# ST-LINK.net
KiCad netlist of a schematic drawn in Altium Designer
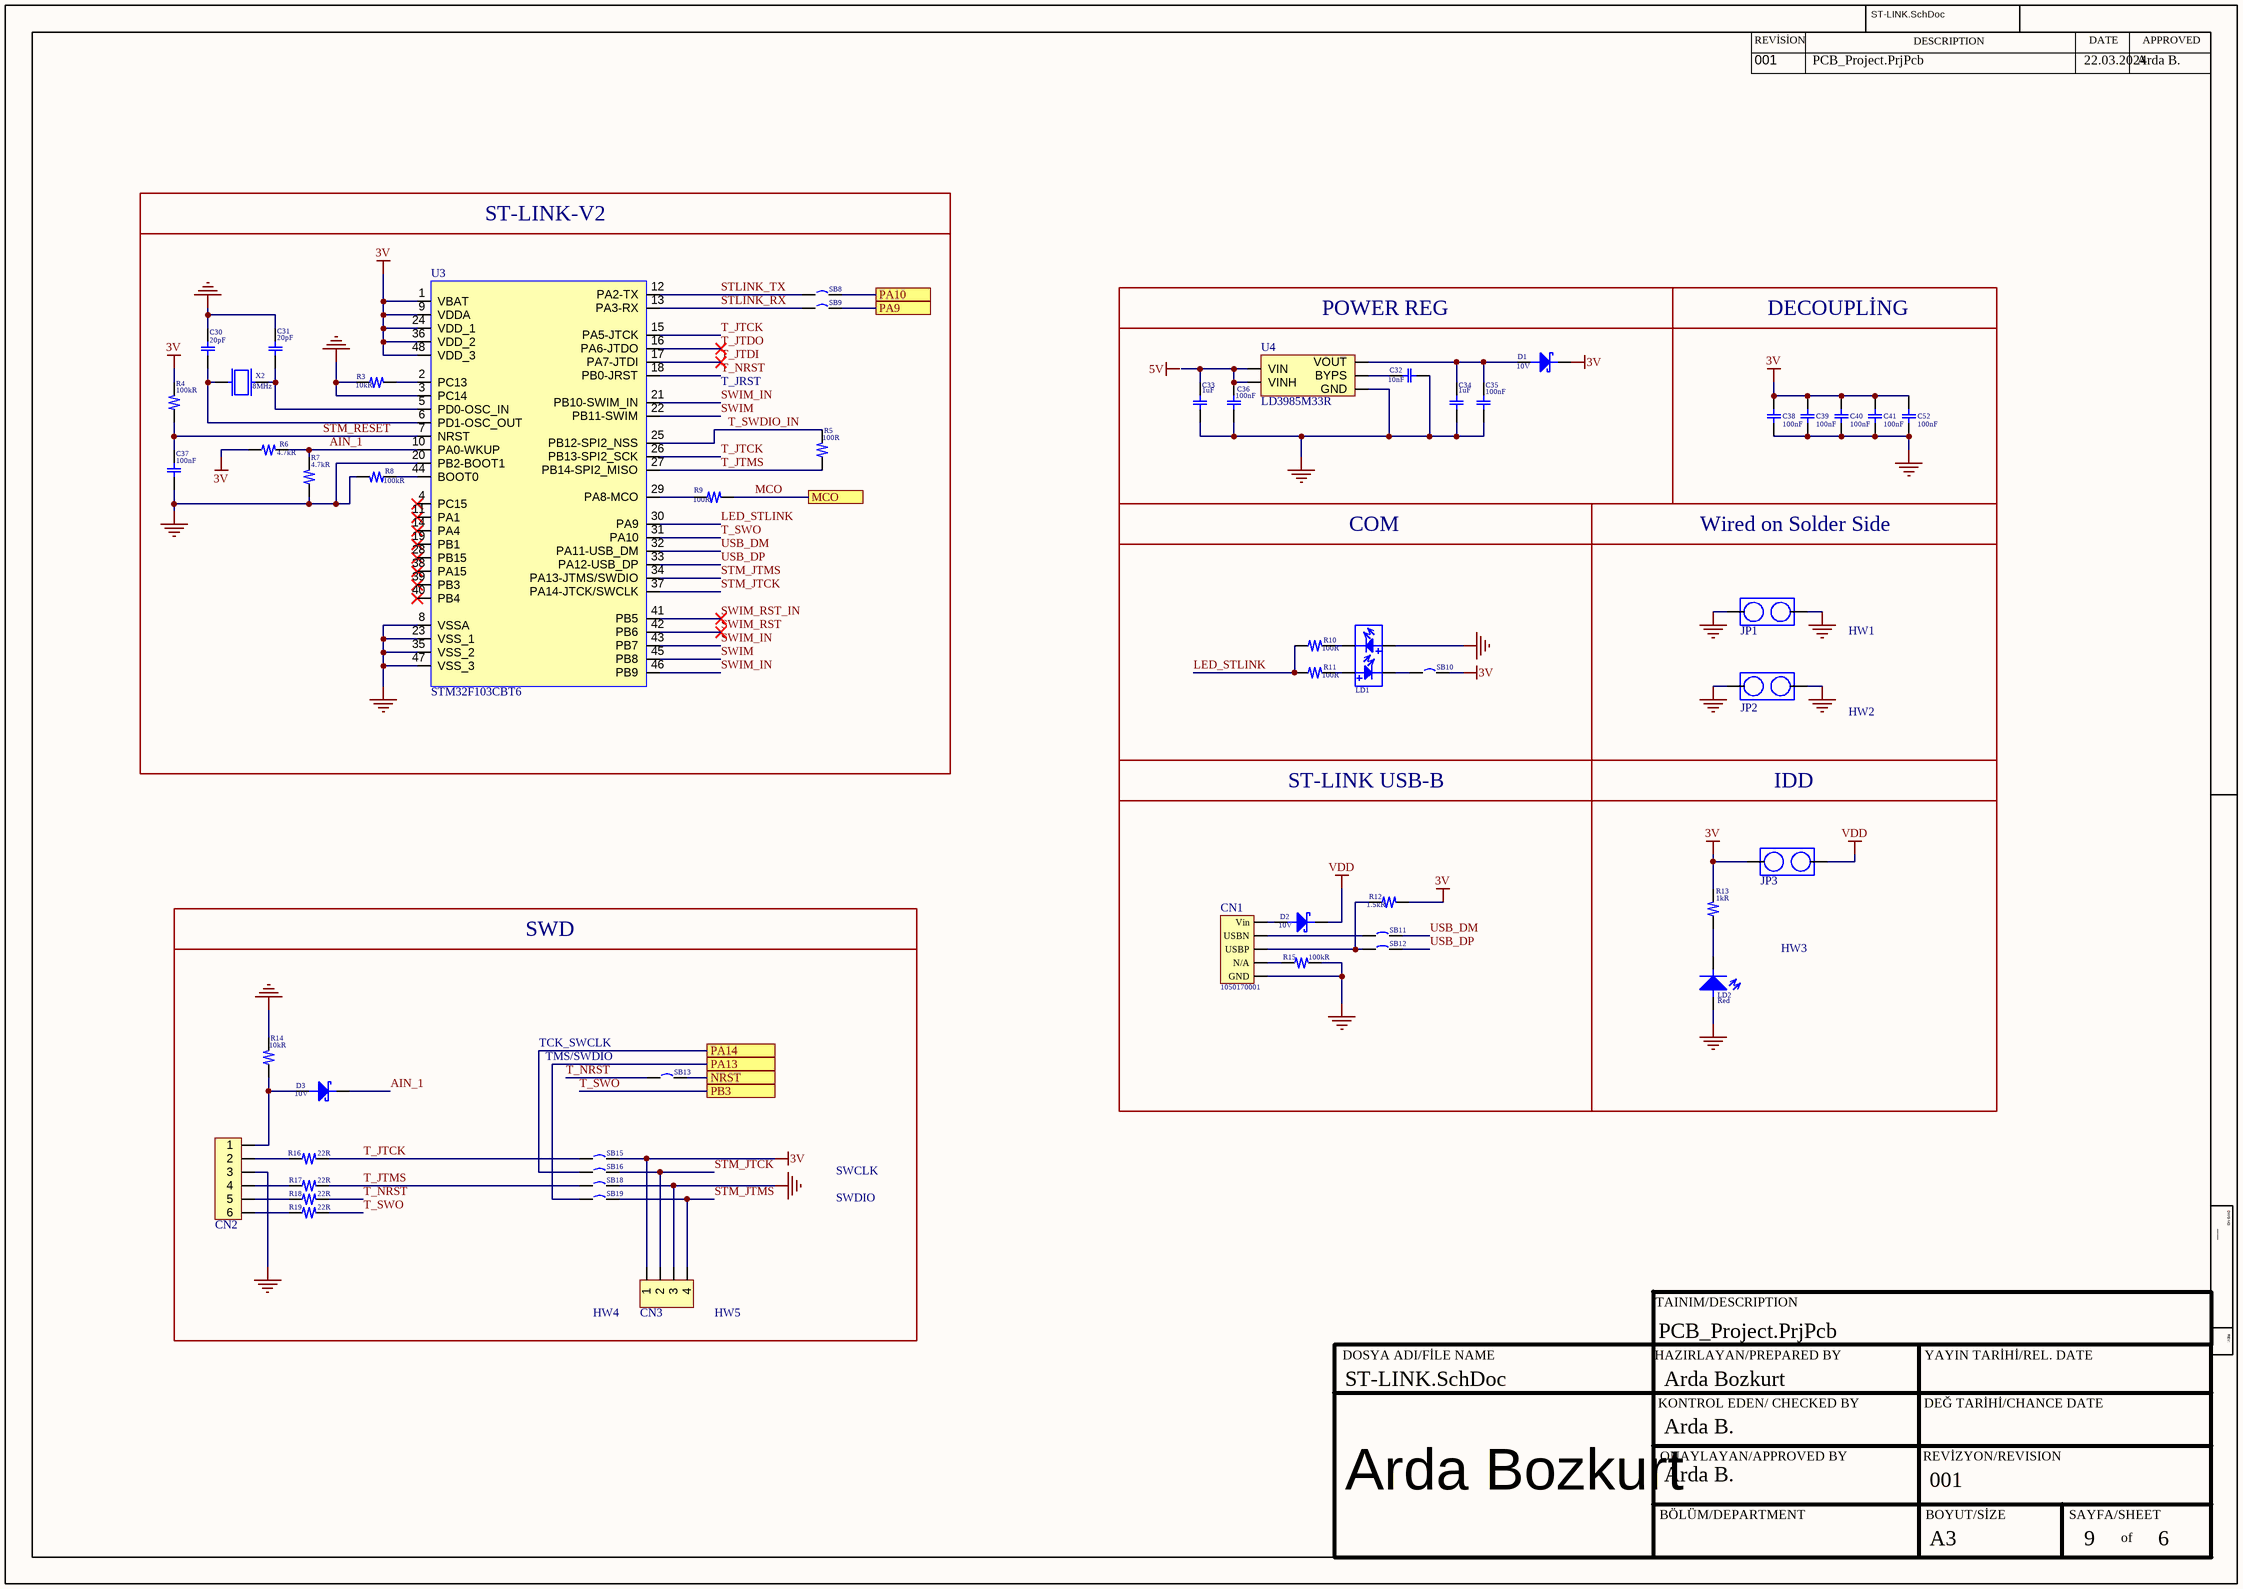
[diagram p0: ST-LINK.SchDoc]

(export (version "E")
  (design (tool "Eeschema 10.0.6"))
  (components
    (comp (ref "C30")
      (value "20pF")
      (footprint "CAP-0402")
      (description "CAP CER 20PF 50V C0G/NPO 0402")
      (fields
        (field (name "MANUFACTURER") "Yageo")
        (field (name "MANUFACTURER PART NUMBER") "CC0402JRNPO9BN200")
      )
      (libsource (lib "STM32") (part "CAP CER 20PF 50V C0G/NPO 0402"))
    )
    (comp (ref "C31")
      (value "20pF")
      (footprint "CAP-0402")
      (description "CAP CER 20PF 50V C0G/NPO 0402")
      (fields
        (field (name "MANUFACTURER") "Yageo")
        (field (name "MANUFACTURER PART NUMBER") "CC0402JRNPO9BN200")
      )
      (libsource (lib "STM32") (part "CAP CER 20PF 50V C0G/NPO 0402"))
    )
    (comp (ref "C32")
      (value "10nF")
      (footprint "CAP-0603")
      (description "Multilayer Ceramic Capacitor, 0.01 uF, 50 V, ± 10%, X7R, 0603 [1608 Metric]")
      (fields
        (field (name "MANUFACTURER") "Yageo")
        (field (name "MANUFACTURER PART NUMBER") "CC0603KRX7R9BB103")
      )
      (libsource (lib "STM32") (part "CAP CER 10nF 50V X7R 0603"))
    )
    (comp (ref "C33")
      (value "1uF")
      (footprint "CAP-0603")
      (description "Multilayer Ceramic Capacitor, 1 uF, 25 V, ± 10%, X5R, 0603 [1608 Metric]")
      (fields
        (field (name "MANUFACTURER") "Yageo")
        (field (name "MANUFACTURER PART NUMBER") "CC0603KRX5R8BB105")
      )
      (libsource (lib "STM32") (part "CAP CER 1UF 25V X5R 0603"))
    )
    (comp (ref "C34")
      (value "1uF")
      (footprint "CAP-0603")
      (description "Multilayer Ceramic Capacitor, 1 uF, 25 V, ± 10%, X5R, 0603 [1608 Metric]")
      (fields
        (field (name "MANUFACTURER") "Yageo")
        (field (name "MANUFACTURER PART NUMBER") "CC0603KRX5R8BB105")
      )
      (libsource (lib "STM32") (part "CAP CER 1UF 25V X5R 0603"))
    )
    (comp (ref "C35")
      (value "100nF")
      (footprint "CAP-0402")
      (description "Multilayer Ceramic Capacitor, 0.1 uF, 25 V, ± 10%, X7R, 0402 [1005 Metric]")
      (fields
        (field (name "MANUFACTURER") "Yageo")
        (field (name "MANUFACTURER PART NUMBER") "CC0402KRX7R7BB104")
      )
      (libsource (lib "STM32") (part "CAP CER 100nF 16V X7R 0402"))
    )
    (comp (ref "C36")
      (value "100nF")
      (footprint "CAP-0402")
      (description "Multilayer Ceramic Capacitor, 0.1 uF, 25 V, ± 10%, X7R, 0402 [1005 Metric]")
      (fields
        (field (name "MANUFACTURER") "Yageo")
        (field (name "MANUFACTURER PART NUMBER") "CC0402KRX7R7BB104")
      )
      (libsource (lib "STM32") (part "CAP CER 100nF 16V X7R 0402"))
    )
    (comp (ref "C37")
      (value "100nF")
      (footprint "CAP-0402")
      (description "Multilayer Ceramic Capacitor, 0.1 uF, 25 V, ± 10%, X7R, 0402 [1005 Metric]")
      (fields
        (field (name "MANUFACTURER") "Yageo")
        (field (name "MANUFACTURER PART NUMBER") "CC0402KRX7R7BB104")
      )
      (libsource (lib "STM32") (part "CAP CER 100nF 16V X7R 0402"))
    )
    (comp (ref "C38")
      (value "100nF")
      (footprint "CAP-0402")
      (description "Multilayer Ceramic Capacitor, 0.1 uF, 25 V, ± 10%, X7R, 0402 [1005 Metric]")
      (fields
        (field (name "MANUFACTURER") "Yageo")
        (field (name "MANUFACTURER PART NUMBER") "CC0402KRX7R7BB104")
      )
      (libsource (lib "STM32") (part "CAP CER 100nF 16V X7R 0402"))
    )
    (comp (ref "C39")
      (value "100nF")
      (footprint "CAP-0402")
      (description "Multilayer Ceramic Capacitor, 0.1 uF, 25 V, ± 10%, X7R, 0402 [1005 Metric]")
      (fields
        (field (name "MANUFACTURER") "Yageo")
        (field (name "MANUFACTURER PART NUMBER") "CC0402KRX7R7BB104")
      )
      (libsource (lib "STM32") (part "CAP CER 100nF 16V X7R 0402"))
    )
    (comp (ref "C40")
      (value "100nF")
      (footprint "CAP-0402")
      (description "Multilayer Ceramic Capacitor, 0.1 uF, 25 V, ± 10%, X7R, 0402 [1005 Metric]")
      (fields
        (field (name "MANUFACTURER") "Yageo")
        (field (name "MANUFACTURER PART NUMBER") "CC0402KRX7R7BB104")
      )
      (libsource (lib "STM32") (part "CAP CER 100nF 16V X7R 0402"))
    )
    (comp (ref "C41")
      (value "100nF")
      (footprint "CAP-0402")
      (description "Multilayer Ceramic Capacitor, 0.1 uF, 25 V, ± 10%, X7R, 0402 [1005 Metric]")
      (fields
        (field (name "MANUFACTURER") "Yageo")
        (field (name "MANUFACTURER PART NUMBER") "CC0402KRX7R7BB104")
      )
      (libsource (lib "STM32") (part "CAP CER 100nF 16V X7R 0402"))
    )
    (comp (ref "C52")
      (value "100nF")
      (footprint "CAP-0402")
      (description "Multilayer Ceramic Capacitor, 0.1 uF, 25 V, ± 10%, X7R, 0402 [1005 Metric]")
      (fields
        (field (name "MANUFACTURER") "Yageo")
        (field (name "MANUFACTURER PART NUMBER") "CC0402KRX7R7BB104")
      )
      (libsource (lib "STM32") (part "CAP CER 100nF 16V X7R 0402"))
    )
    (comp (ref "CN1")
      (value "1050170001")
      (footprint "USB MİCRO B")
      (description "Conn Micro USB 2.0 Type B RCP 5 POS 0.65mm Solder RA SMD 5 Terminal 1 Port Micro-USB T/R")
      (fields (field (name "MANUFACTURER") "Molex"))
      (libsource (lib "STM32") (part "CONN USB MICRO B SMD"))
    )
    (comp (ref "CN2")
      (value "TS-106-G-A")
      (footprint "CONN-6POS")
      (description "Conn Unshrouded Header HDR 6 POS 2.54mm Solder ST Top Entry Thru-Hole Tube")
      (fields (field (name "MANUFACTURER") "Samtec"))
      (libsource (lib "STM32") (part "CONN 6POS"))
    )
    (comp (ref "CN3")
      (value "61300411121")
      (footprint "CONN-4POS")
      (description "THT Vertical Pin Header WR-PHD, Pitch 2.54 mm, Single Row, 4 pins")
      (fields (field (name "MANUFACTURER") "Wurth Electronics"))
      (libsource (lib "STM32") (part "CONN 4POS GOLD"))
    )
    (comp (ref "D1")
      (value "BAT60JFILM")
      (footprint "SOD-323")
      (description "Rectifier Diode, Schottky, 1 Phase, 1 Element, 3A, 10V V(RRM), Silicon")
      (fields (field (name "MANUFACTURER") "STMicroelectronics") (field (name "PEAK VOLTAGE") "10V"))
      (libsource (lib "STM32") (part "DIODE SCHOTTKY 10V 3A SOD323"))
    )
    (comp (ref "D2")
      (value "BAT60JFILM")
      (footprint "SOD-323")
      (description "Rectifier Diode, Schottky, 1 Phase, 1 Element, 3A, 10V V(RRM), Silicon")
      (fields (field (name "MANUFACTURER") "STMicroelectronics") (field (name "PEAK VOLTAGE") "10V"))
      (libsource (lib "STM32") (part "DIODE SCHOTTKY 10V 3A SOD323"))
    )
    (comp (ref "D3")
      (value "BAT60JFILM")
      (footprint "SOD-323")
      (description "Rectifier Diode, Schottky, 1 Phase, 1 Element, 3A, 10V V(RRM), Silicon")
      (fields (field (name "MANUFACTURER") "STMicroelectronics") (field (name "PEAK VOLTAGE") "10V"))
      (libsource (lib "STM32") (part "DIODE SCHOTTKY 10V 3A SOD323"))
    )
    (comp (ref "HW1")
      (value "MNT-101-BK-G")
      (footprint "SHUNT")
      (description "MNT - Samtec 2.54mm Multi Position Jumper Link / Shunt")
      (fields (field (name "MANUFACTURER") "Samtec"))
      (libsource (lib "STM32") (part "SHUNT"))
    )
    (comp (ref "HW2")
      (value "MNT-101-BK-G")
      (footprint "SHUNT")
      (description "MNT - Samtec 2.54mm Multi Position Jumper Link / Shunt")
      (fields (field (name "MANUFACTURER") "Samtec"))
      (libsource (lib "STM32") (part "SHUNT"))
    )
    (comp (ref "HW3")
      (value "MNT-101-BK-G")
      (footprint "SHUNT")
      (description "MNT - Samtec 2.54mm Multi Position Jumper Link / Shunt")
      (fields (field (name "MANUFACTURER") "Samtec"))
      (libsource (lib "STM32") (part "SHUNT"))
    )
    (comp (ref "HW4")
      (value "MNT-101-BK-G")
      (footprint "SHUNT")
      (description "MNT - Samtec 2.54mm Multi Position Jumper Link / Shunt")
      (fields (field (name "MANUFACTURER") "Samtec"))
      (libsource (lib "STM32") (part "SHUNT"))
    )
    (comp (ref "HW5")
      (value "MNT-101-BK-G")
      (footprint "SHUNT")
      (description "MNT - Samtec 2.54mm Multi Position Jumper Link / Shunt")
      (fields (field (name "MANUFACTURER") "Samtec"))
      (libsource (lib "STM32") (part "SHUNT"))
    )
    (comp (ref "JP1")
      (value "61300211121")
      (footprint "CONN-2PİNS")
      (description "THT Vertical Pin Header WR-PHD, Pitch 2.54 mm, Single Row, 2 pins")
      (fields (field (name "MANUFACTURER") "Wurth Electronics"))
      (libsource (lib "STM32") (part "CONN HEADER VERT 2POS 2.54MM"))
    )
    (comp (ref "JP2")
      (value "61300211121")
      (footprint "CONN-2PİNS")
      (description "THT Vertical Pin Header WR-PHD, Pitch 2.54 mm, Single Row, 2 pins")
      (fields (field (name "MANUFACTURER") "Wurth Electronics"))
      (libsource (lib "STM32") (part "CONN HEADER VERT 2POS 2.54MM"))
    )
    (comp (ref "JP3")
      (value "61300211121")
      (footprint "CONN-2PİNS")
      (description "THT Vertical Pin Header WR-PHD, Pitch 2.54 mm, Single Row, 2 pins")
      (fields (field (name "MANUFACTURER") "Wurth Electronics"))
      (libsource (lib "STM32") (part "CONN HEADER VERT 2POS 2.54MM"))
    )
    (comp (ref "LD1")
      (value "67-22SURSYGC/S530-A2/TR8")
      (footprint "LED-RED-GREEN-SMD")
      (description "LED Bi-Color Red/Yellow Green 632nm/575nm 4-Pin PLCC T/R")
      (fields (field (name "MANUFACTURER") "Everlight"))
      (libsource (lib "STM32") (part "LED Red/Yellow-Green SMD"))
    )
    (comp (ref "LD2")
      (value "150060RS75000")
      (footprint "LED-RED-0603")
      (description "LED Low-Power Uni-Color Red 630nm 2V 2-Pin Chip 0603(1608Metric) T/R")
      (fields (field (name "MANUFACTURER") "Wurth Electronics") (field (name "COLOR") "Red"))
      (libsource (lib "STM32") (part "LED RED CLEAR 0603 SMD"))
    )
    (comp (ref "R3")
      (value "10kR")
      (footprint "RES-0402")
      (description "SMD Chip Resistor, 10 kOhm, ± 1%, 63 mW, 0402 [1005 Metric], Thick Film, General Purpose")
      (fields
        (field (name "MANUFACTURER") "Yageo")
        (field (name "MANUFACTURER PART NUMBER") "RC0402FR-0710KL")
      )
      (libsource (lib "STM32") (part "RES 10K OHM 1% 1/16W 0402"))
    )
    (comp (ref "R4")
      (value "100kR")
      (footprint "RES-0402")
      (description "SMD Chip Resistor, 100 kOhm, ± 1%, 63 mW, 0402 [1005 Metric], Thick Film, General Purpose")
      (fields
        (field (name "MANUFACTURER") "Yageo")
        (field (name "MANUFACTURER PART NUMBER") "RC0402FR-07100KL")
      )
      (libsource (lib "STM32") (part "RES 100K OHM 1% 1/16W 0402"))
    )
    (comp (ref "R5")
      (value "100R")
      (footprint "RES-0402")
      (description "SMD Chip Resistor, 100 Ohm, ± 1%, 63 mW, 0402 [1005 Metric], Thick Film, General Purpose")
      (fields
        (field (name "MANUFACTURER") "Yageo")
        (field (name "MANUFACTURER PART NUMBER") "RC0402FR-07100RL")
      )
      (libsource (lib "STM32") (part "RES 100 OHM 1% 1/16W 0402"))
    )
    (comp (ref "R6")
      (value "4.7kR")
      (footprint "RES-0402")
      (description "SMD Chip Resistor, 4.7 kOhm, ± 1%, 63 mW, 0402 [1005 Metric], Thick Film, General Purpose")
      (fields
        (field (name "MANUFACTURER") "Yageo")
        (field (name "MANUFACTURER PART NUMBER") "RC0402FR-074K7L")
      )
      (libsource (lib "STM32") (part "RES 4.7K OHM 1% 1/16W 0402"))
    )
    (comp (ref "R7")
      (value "4.7kR")
      (footprint "RES-0402")
      (description "SMD Chip Resistor, 4.7 kOhm, ± 1%, 63 mW, 0402 [1005 Metric], Thick Film, General Purpose")
      (fields
        (field (name "MANUFACTURER") "Yageo")
        (field (name "MANUFACTURER PART NUMBER") "RC0402FR-074K7L")
      )
      (libsource (lib "STM32") (part "RES 4.7K OHM 1% 1/16W 0402"))
    )
    (comp (ref "R8")
      (value "100kR")
      (footprint "RES-0402")
      (description "SMD Chip Resistor, 100 kOhm, ± 1%, 63 mW, 0402 [1005 Metric], Thick Film, General Purpose")
      (fields
        (field (name "MANUFACTURER") "Yageo")
        (field (name "MANUFACTURER PART NUMBER") "RC0402FR-07100KL")
      )
      (libsource (lib "STM32") (part "RES 100K OHM 1% 1/16W 0402"))
    )
    (comp (ref "R9")
      (value "100R")
      (footprint "RES-0402")
      (description "SMD Chip Resistor, 100 Ohm, ± 1%, 63 mW, 0402 [1005 Metric], Thick Film, General Purpose")
      (fields
        (field (name "MANUFACTURER") "Yageo")
        (field (name "MANUFACTURER PART NUMBER") "RC0402FR-07100RL")
      )
      (libsource (lib "STM32") (part "RES 100 OHM 1% 1/16W 0402"))
    )
    (comp (ref "R10")
      (value "100R")
      (footprint "RES-0402")
      (description "SMD Chip Resistor, 100 Ohm, ± 1%, 63 mW, 0402 [1005 Metric], Thick Film, General Purpose")
      (fields
        (field (name "MANUFACTURER") "Yageo")
        (field (name "MANUFACTURER PART NUMBER") "RC0402FR-07100RL")
      )
      (libsource (lib "STM32") (part "RES 100 OHM 1% 1/16W 0402"))
    )
    (comp (ref "R11")
      (value "100R")
      (footprint "RES-0402")
      (description "SMD Chip Resistor, 100 Ohm, ± 1%, 63 mW, 0402 [1005 Metric], Thick Film, General Purpose")
      (fields
        (field (name "MANUFACTURER") "Yageo")
        (field (name "MANUFACTURER PART NUMBER") "RC0402FR-07100RL")
      )
      (libsource (lib "STM32") (part "RES 100 OHM 1% 1/16W 0402"))
    )
    (comp (ref "R12")
      (value "1.5kR")
      (footprint "RES-0402")
      (description "SMD Chip Resistor, 1.5 kOhm, ± 1%, 63 mW, 0402 [1005 Metric], Thick Film, General Purpose")
      (fields
        (field (name "MANUFACTURER") "Yageo")
        (field (name "MANUFACTURER PART NUMBER") "RC0402FR-071K5L")
      )
      (libsource (lib "STM32") (part "RES 1.5K OHM 1% 1/16W 0402"))
    )
    (comp (ref "R13")
      (value "1kR")
      (footprint "RES-0402")
      (description "SMD Chip Resistor, 1 kOhm, ± 1%, 63 mW, 0402 [1005 Metric], Thick Film, General Purpose")
      (fields
        (field (name "MANUFACTURER") "Yageo")
        (field (name "MANUFACTURER PART NUMBER") "RC0402FR-071KL")
      )
      (libsource (lib "STM32") (part "RES 1K OHM 1% 1/16W 0402"))
    )
    (comp (ref "R14")
      (value "10kR")
      (footprint "RES-0402")
      (description "SMD Chip Resistor, 10 kOhm, ± 1%, 63 mW, 0402 [1005 Metric], Thick Film, General Purpose")
      (fields
        (field (name "MANUFACTURER") "Yageo")
        (field (name "MANUFACTURER PART NUMBER") "RC0402FR-0710KL")
      )
      (libsource (lib "STM32") (part "RES 10K OHM 1% 1/16W 0402"))
    )
    (comp (ref "R15")
      (value "100kR")
      (footprint "RES-0402")
      (description "SMD Chip Resistor, 100 kOhm, ± 1%, 63 mW, 0402 [1005 Metric], Thick Film, General Purpose")
      (fields
        (field (name "MANUFACTURER") "Yageo")
        (field (name "MANUFACTURER PART NUMBER") "RC0402FR-07100KL")
      )
      (libsource (lib "STM32") (part "RES 100K OHM 1% 1/16W 0402"))
    )
    (comp (ref "R16")
      (value "22R")
      (footprint "RES-0603")
      (description "SMD Chip Resistor, 22 Ohm, ± 1%, 100 mW, 0603 [1608 Metric], Thick Film, General Purpose")
      (fields
        (field (name "MANUFACTURER") "Yageo")
        (field (name "MANUFACTURER PART NUMBER") "RC0603FR-0722RL")
      )
      (libsource (lib "STM32") (part "RES 22 OHM 1% 1/10W 0603"))
    )
    (comp (ref "R17")
      (value "22R")
      (footprint "RES-0603")
      (description "SMD Chip Resistor, 22 Ohm, ± 1%, 100 mW, 0603 [1608 Metric], Thick Film, General Purpose")
      (fields
        (field (name "MANUFACTURER") "Yageo")
        (field (name "MANUFACTURER PART NUMBER") "RC0603FR-0722RL")
      )
      (libsource (lib "STM32") (part "RES 22 OHM 1% 1/10W 0603"))
    )
    (comp (ref "R18")
      (value "22R")
      (footprint "RES-0603")
      (description "SMD Chip Resistor, 22 Ohm, ± 1%, 100 mW, 0603 [1608 Metric], Thick Film, General Purpose")
      (fields
        (field (name "MANUFACTURER") "Yageo")
        (field (name "MANUFACTURER PART NUMBER") "RC0603FR-0722RL")
      )
      (libsource (lib "STM32") (part "RES 22 OHM 1% 1/10W 0603"))
    )
    (comp (ref "R19")
      (value "22R")
      (footprint "RES-0603")
      (description "SMD Chip Resistor, 22 Ohm, ± 1%, 100 mW, 0603 [1608 Metric], Thick Film, General Purpose")
      (fields
        (field (name "MANUFACTURER") "Yageo")
        (field (name "MANUFACTURER PART NUMBER") "RC0603FR-0722RL")
      )
      (libsource (lib "STM32") (part "RES 22 OHM 1% 1/10W 0603"))
    )
    (comp (ref "SB8")
      (value "RC0402JR-070RL")
      (footprint "RES-0402")
      (description "Zero Ohm Resistor, Jumper, 0402 [1005 Metric], Thick Film, 62.5 mW, 1 A, Surface Mount")
      (fields
        (field (name "MANUFACTURER") "Yageo")
        (field (name "MANUFACTURER PART NUMBER") "RC0603JR-070RL")
      )
      (libsource (lib "STM32") (part "RES 0 OHM JUMPER 1/10W 0603"))
    )
    (comp (ref "SB9")
      (value "RC0402JR-070RL")
      (footprint "RES-0402")
      (description "Zero Ohm Resistor, Jumper, 0402 [1005 Metric], Thick Film, 62.5 mW, 1 A, Surface Mount")
      (fields
        (field (name "MANUFACTURER") "Yageo")
        (field (name "MANUFACTURER PART NUMBER") "RC0603JR-070RL")
      )
      (libsource (lib "STM32") (part "RES 0 OHM JUMPER 1/10W 0603"))
    )
    (comp (ref "SB10")
      (value "RC0402JR-070RL")
      (footprint "RES-0402")
      (description "Zero Ohm Resistor, Jumper, 0402 [1005 Metric], Thick Film, 62.5 mW, 1 A, Surface Mount")
      (fields
        (field (name "MANUFACTURER") "Yageo")
        (field (name "MANUFACTURER PART NUMBER") "RC0603JR-070RL")
      )
      (libsource (lib "STM32") (part "RES 0 OHM JUMPER 1/10W 0603"))
    )
    (comp (ref "SB11")
      (value "RC0402JR-070RL")
      (footprint "RES-0402")
      (description "Zero Ohm Resistor, Jumper, 0402 [1005 Metric], Thick Film, 62.5 mW, 1 A, Surface Mount")
      (fields
        (field (name "MANUFACTURER") "Yageo")
        (field (name "MANUFACTURER PART NUMBER") "RC0603JR-070RL")
      )
      (libsource (lib "STM32") (part "RES 0 OHM JUMPER 1/10W 0603"))
    )
    (comp (ref "SB12")
      (value "RC0402JR-070RL")
      (footprint "RES-0402")
      (description "Zero Ohm Resistor, Jumper, 0402 [1005 Metric], Thick Film, 62.5 mW, 1 A, Surface Mount")
      (fields
        (field (name "MANUFACTURER") "Yageo")
        (field (name "MANUFACTURER PART NUMBER") "RC0603JR-070RL")
      )
      (libsource (lib "STM32") (part "RES 0 OHM JUMPER 1/10W 0603"))
    )
    (comp (ref "SB13")
      (value "RC0402JR-070RL")
      (footprint "RES-0402")
      (description "Zero Ohm Resistor, Jumper, 0402 [1005 Metric], Thick Film, 62.5 mW, 1 A, Surface Mount")
      (fields
        (field (name "MANUFACTURER") "Yageo")
        (field (name "MANUFACTURER PART NUMBER") "RC0603JR-070RL")
      )
      (libsource (lib "STM32") (part "RES 0 OHM JUMPER 1/10W 0603"))
    )
    (comp (ref "SB15")
      (value "RC0402JR-070RL")
      (footprint "RES-0402")
      (description "Zero Ohm Resistor, Jumper, 0402 [1005 Metric], Thick Film, 62.5 mW, 1 A, Surface Mount")
      (fields
        (field (name "MANUFACTURER") "Yageo")
        (field (name "MANUFACTURER PART NUMBER") "RC0603JR-070RL")
      )
      (libsource (lib "STM32") (part "RES 0 OHM JUMPER 1/10W 0603"))
    )
    (comp (ref "SB16")
      (value "RC0402JR-070RL")
      (footprint "RES-0402")
      (description "Zero Ohm Resistor, Jumper, 0402 [1005 Metric], Thick Film, 62.5 mW, 1 A, Surface Mount")
      (fields
        (field (name "MANUFACTURER") "Yageo")
        (field (name "MANUFACTURER PART NUMBER") "RC0603JR-070RL")
      )
      (libsource (lib "STM32") (part "RES 0 OHM JUMPER 1/10W 0603"))
    )
    (comp (ref "SB18")
      (value "RC0402JR-070RL")
      (footprint "RES-0402")
      (description "Zero Ohm Resistor, Jumper, 0402 [1005 Metric], Thick Film, 62.5 mW, 1 A, Surface Mount")
      (fields
        (field (name "MANUFACTURER") "Yageo")
        (field (name "MANUFACTURER PART NUMBER") "RC0603JR-070RL")
      )
      (libsource (lib "STM32") (part "RES 0 OHM JUMPER 1/10W 0603"))
    )
    (comp (ref "SB19")
      (value "RC0402JR-070RL")
      (footprint "RES-0402")
      (description "Zero Ohm Resistor, Jumper, 0402 [1005 Metric], Thick Film, 62.5 mW, 1 A, Surface Mount")
      (fields
        (field (name "MANUFACTURER") "Yageo")
        (field (name "MANUFACTURER PART NUMBER") "RC0603JR-070RL")
      )
      (libsource (lib "STM32") (part "RES 0 OHM JUMPER 1/10W 0603"))
    )
    (comp (ref "U3")
      (value "STM32F103CBT6")
      (footprint "LQFP-48")
      (description "ARM Cortex-M3 STM32 F1 Microcontroller 32-Bit 72MHz 128kB FLASH LQFP48 STM32F103CBT6")
      (fields (field (name "MANUFACTURER") "STMicroelectronics"))
      (libsource (lib "STM32") (part "IC MCU 32BIT 128KB FLASH 48LQFP"))
    )
    (comp (ref "U4")
      (value "LD3985M33R")
      (footprint "SOT23-5L")
      (description "LD3985 Series 150 mA 3.3 V Fixed Low Noise LDO BiCMOS Regulator-SOT-23-5")
      (fields (field (name "MANUFACTURER") "STMicroelectronics"))
      (libsource (lib "STM32") (part "IC REG LINEAR 3.3V 150MA SOT23-5"))
    )
    (comp (ref "X2")
      (value "H1OED8K5SC-112YXC-8M")
      (footprint "HC-49US")
      (description "HC-49US 8MHZ 20PF 20PPM H1OED8K5")
      (fields (field (name "MANUFACTURER") "YXC") (field (name "FREQUENCY") "8MHz"))
      (libsource (lib "STM32") (part "Crystal 8MHZ 20PF 20PPM H1OED8K5"))
    )
  )
  (nets
    (net (code "1") (name "/AIN_1") (class "Default")
      (node (ref "D3") (pin "1") (pinfunction "1_1") (pintype "passive"))
      (node (ref "R6") (pin "2") (pinfunction "2_2") (pintype "passive"))
      (node (ref "R7") (pin "2") (pinfunction "2_2") (pintype "passive"))
      (node (ref "U3") (pin "10") (pinfunction "PA0-WKUP_10") (pintype "passive"))
    )
    (net (code "2") (name "/LED_STLINK") (class "Default")
      (node (ref "R10") (pin "1") (pinfunction "1_1") (pintype "passive"))
      (node (ref "R11") (pin "1") (pinfunction "1_1") (pintype "passive"))
      (node (ref "U3") (pin "30") (pinfunction "PA9_30") (pintype "passive"))
    )
    (net (code "3") (name "/MCO") (class "Default")
      (node (ref "R9") (pin "2") (pinfunction "2_2") (pintype "passive"))
    )
    (net (code "4") (name "/NRST") (class "Default")
      (node (ref "SB13") (pin "2") (pinfunction "2_2") (pintype "passive"))
    )
    (net (code "5") (name "/PA9") (class "Default")
      (node (ref "SB9") (pin "2") (pinfunction "2_2") (pintype "passive"))
    )
    (net (code "6") (name "/PA10") (class "Default")
      (node (ref "SB8") (pin "2") (pinfunction "2_2") (pintype "passive"))
    )
    (net (code "7") (name "/PA13") (class "Default")
      (node (ref "SB19") (pin "1") (pinfunction "1_1") (pintype "passive"))
    )
    (net (code "8") (name "/PA14") (class "Default")
      (node (ref "SB16") (pin "1") (pinfunction "1_1") (pintype "passive"))
    )
    (net (code "9") (name "/STLINK_RX") (class "Default")
      (node (ref "SB9") (pin "1") (pinfunction "1_1") (pintype "passive"))
      (node (ref "U3") (pin "13") (pinfunction "PA3-RX_13") (pintype "passive"))
    )
    (net (code "10") (name "/STLINK_TX") (class "Default")
      (node (ref "SB8") (pin "1") (pinfunction "1_1") (pintype "passive"))
      (node (ref "U3") (pin "12") (pinfunction "PA2-TX_12") (pintype "passive"))
    )
    (net (code "11") (name "/STM_JTCK") (class "Default")
      (node (ref "CN3") (pin "2") (pinfunction "2_2") (pintype "passive"))
      (node (ref "SB16") (pin "2") (pinfunction "2_2") (pintype "passive"))
      (node (ref "U3") (pin "37") (pinfunction "PA14-JTCK/SWCLK_37") (pintype "passive"))
    )
    (net (code "12") (name "/STM_JTMS") (class "Default")
      (node (ref "CN3") (pin "4") (pinfunction "4_4") (pintype "passive"))
      (node (ref "SB19") (pin "2") (pinfunction "2_2") (pintype "passive"))
      (node (ref "U3") (pin "34") (pinfunction "PA13-JTMS/SWDIO_34") (pintype "passive"))
    )
    (net (code "13") (name "/STM_RESET") (class "Default")
      (node (ref "C37") (pin "2") (pinfunction "2_2") (pintype "passive"))
      (node (ref "R4") (pin "1") (pinfunction "1_1") (pintype "passive"))
      (node (ref "U3") (pin "7") (pinfunction "NRST_7") (pintype "passive"))
    )
    (net (code "14") (name "/SWIM") (class "Default")
      (node (ref "U3") (pin "22") (pinfunction "PB11-SWIM_22") (pintype "passive"))
      (node (ref "U3") (pin "45") (pinfunction "PB8_45") (pintype "passive"))
    )
    (net (code "15") (name "/SWIM_IN") (class "Default")
      (node (ref "U3") (pin "21") (pinfunction "PB10-SWIM_IN_21") (pintype "passive"))
      (node (ref "U3") (pin "43") (pinfunction "PB7_43") (pintype "passive"))
      (node (ref "U3") (pin "46") (pinfunction "PB9_46") (pintype "passive"))
    )
    (net (code "16") (name "/SWIM_RST") (class "Default")
      (node (ref "U3") (pin "42") (pinfunction "PB6_42") (pintype "passive+no_connect"))
    )
    (net (code "17") (name "/SWIM_RST_IN") (class "Default")
      (node (ref "U3") (pin "41") (pinfunction "PB5_41") (pintype "passive+no_connect"))
    )
    (net (code "18") (name "/T_JTCK") (class "Default")
      (node (ref "R16") (pin "2") (pinfunction "2_2") (pintype "passive"))
      (node (ref "SB15") (pin "1") (pinfunction "1_1") (pintype "passive"))
      (node (ref "U3") (pin "15") (pinfunction "PA5-JTCK_15") (pintype "passive"))
      (node (ref "U3") (pin "26") (pinfunction "PB13-SPI2_SCK_26") (pintype "passive"))
    )
    (net (code "19") (name "/T_JTDI") (class "Default")
      (node (ref "U3") (pin "17") (pinfunction "PA7-JTDI_17") (pintype "passive+no_connect"))
    )
    (net (code "20") (name "/T_JTDO") (class "Default")
      (node (ref "U3") (pin "16") (pinfunction "PA6-JTDO_16") (pintype "passive+no_connect"))
    )
    (net (code "21") (name "/T_JTMS") (class "Default")
      (node (ref "R17") (pin "2") (pinfunction "2_2") (pintype "passive"))
      (node (ref "R5") (pin "1") (pinfunction "1_1") (pintype "passive"))
      (node (ref "SB18") (pin "1") (pinfunction "1_1") (pintype "passive"))
      (node (ref "U3") (pin "27") (pinfunction "PB14-SPI2_MISO_27") (pintype "passive"))
    )
    (net (code "22") (name "/T_NRST") (class "Default")
      (node (ref "R18") (pin "2") (pinfunction "2_2") (pintype "passive"))
      (node (ref "SB13") (pin "1") (pinfunction "1_1") (pintype "passive"))
      (node (ref "U3") (pin "18") (pinfunction "PB0-JRST_18") (pintype "passive"))
    )
    (net (code "23") (name "/T_SWDIO_IN") (class "Default")
      (node (ref "R5") (pin "2") (pinfunction "2_2") (pintype "passive"))
      (node (ref "U3") (pin "25") (pinfunction "PB12-SPI2_NSS_25") (pintype "passive"))
    )
    (net (code "24") (name "/T_SWO") (class "Default")
      (node (ref "R19") (pin "2") (pinfunction "2_2") (pintype "passive"))
      (node (ref "U3") (pin "31") (pinfunction "PA10_31") (pintype "passive"))
    )
    (net (code "25") (name "/USB_DM") (class "Default")
      (node (ref "SB11") (pin "2") (pinfunction "2_2") (pintype "passive"))
      (node (ref "U3") (pin "32") (pinfunction "PA11-USB_DM_32") (pintype "passive"))
    )
    (net (code "26") (name "/USB_DP") (class "Default")
      (node (ref "SB12") (pin "2") (pinfunction "2_2") (pintype "passive"))
      (node (ref "U3") (pin "33") (pinfunction "PA12-USB_DP_33") (pintype "passive"))
    )
    (net (code "27") (name "3V") (class "Default")
      (node (ref "C38") (pin "2") (pinfunction "2_2") (pintype "passive"))
      (node (ref "C39") (pin "2") (pinfunction "2_2") (pintype "passive"))
      (node (ref "C40") (pin "2") (pinfunction "2_2") (pintype "passive"))
      (node (ref "C41") (pin "2") (pinfunction "2_2") (pintype "passive"))
      (node (ref "C52") (pin "2") (pinfunction "2_2") (pintype "passive"))
      (node (ref "CN3") (pin "1") (pinfunction "1_1") (pintype "passive"))
      (node (ref "D1") (pin "1") (pinfunction "1_1") (pintype "passive"))
      (node (ref "JP3") (pin "1") (pinfunction "1_1") (pintype "passive"))
      (node (ref "R12") (pin "2") (pinfunction "2_2") (pintype "passive"))
      (node (ref "R13") (pin "2") (pinfunction "2_2") (pintype "passive"))
      (node (ref "R4") (pin "2") (pinfunction "2_2") (pintype "passive"))
      (node (ref "R6") (pin "1") (pinfunction "1_1") (pintype "passive"))
      (node (ref "SB10") (pin "2") (pinfunction "2_2") (pintype "passive"))
      (node (ref "SB15") (pin "2") (pinfunction "2_2") (pintype "passive"))
      (node (ref "U3") (pin "1") (pinfunction "VBAT_1") (pintype "passive"))
      (node (ref "U3") (pin "24") (pinfunction "VDD_1_24") (pintype "passive"))
      (node (ref "U3") (pin "36") (pinfunction "VDD_2_36") (pintype "passive"))
      (node (ref "U3") (pin "48") (pinfunction "VDD_3_48") (pintype "passive"))
      (node (ref "U3") (pin "9") (pinfunction "VDDA_9") (pintype "passive"))
    )
    (net (code "29") (name "GND") (class "Default")
      (node (ref "C30") (pin "2") (pinfunction "2_2") (pintype "passive"))
      (node (ref "C31") (pin "2") (pinfunction "2_2") (pintype "passive"))
      (node (ref "C32") (pin "2") (pinfunction "2_2") (pintype "passive"))
      (node (ref "C33") (pin "1") (pinfunction "1_1") (pintype "passive"))
      (node (ref "C34") (pin "1") (pinfunction "1_1") (pintype "passive"))
      (node (ref "C35") (pin "1") (pinfunction "1_1") (pintype "passive"))
      (node (ref "C36") (pin "1") (pinfunction "1_1") (pintype "passive"))
      (node (ref "C37") (pin "1") (pinfunction "1_1") (pintype "passive"))
      (node (ref "C38") (pin "1") (pinfunction "1_1") (pintype "passive"))
      (node (ref "C39") (pin "1") (pinfunction "1_1") (pintype "passive"))
      (node (ref "C40") (pin "1") (pinfunction "1_1") (pintype "passive"))
      (node (ref "C41") (pin "1") (pinfunction "1_1") (pintype "passive"))
      (node (ref "C52") (pin "1") (pinfunction "1_1") (pintype "passive"))
      (node (ref "CN1") (pin "5") (pinfunction "GND_5") (pintype "passive"))
      (node (ref "CN2") (pin "3") (pinfunction "3_3") (pintype "passive"))
      (node (ref "CN3") (pin "3") (pinfunction "3_3") (pintype "passive"))
      (node (ref "JP1") (pin "1") (pinfunction "1_1") (pintype "passive"))
      (node (ref "JP1") (pin "2") (pinfunction "2_2") (pintype "passive"))
      (node (ref "JP2") (pin "1") (pinfunction "1_1") (pintype "passive"))
      (node (ref "JP2") (pin "2") (pinfunction "2_2") (pintype "passive"))
      (node (ref "LD1") (pin "1") (pinfunction "1_1") (pintype "passive"))
      (node (ref "LD2") (pin "2") (pinfunction "2_2") (pintype "passive"))
      (node (ref "R14") (pin "2") (pinfunction "2_2") (pintype "passive"))
      (node (ref "R15") (pin "2") (pinfunction "2_2") (pintype "passive"))
      (node (ref "R3") (pin "1") (pinfunction "1_1") (pintype "passive"))
      (node (ref "R7") (pin "1") (pinfunction "1_1") (pintype "passive"))
      (node (ref "R8") (pin "2") (pinfunction "2_2") (pintype "passive"))
      (node (ref "SB18") (pin "2") (pinfunction "2_2") (pintype "passive"))
      (node (ref "U3") (pin "20") (pinfunction "PB2-BOOT1_20") (pintype "passive"))
      (node (ref "U3") (pin "23") (pinfunction "VSS_1_23") (pintype "passive"))
      (node (ref "U3") (pin "3") (pinfunction "PC14_3") (pintype "passive"))
      (node (ref "U3") (pin "35") (pinfunction "VSS_2_35") (pintype "passive"))
      (node (ref "U3") (pin "47") (pinfunction "VSS_3_47") (pintype "passive"))
      (node (ref "U3") (pin "8") (pinfunction "VSSA_8") (pintype "passive"))
      (node (ref "U4") (pin "2") (pinfunction "GND_2") (pintype "passive"))
    )
    (net (code "30") (name "Net-(CN1-N{slash}A)") (class "Default")
      (node (ref "CN1") (pin "4") (pinfunction "N/A_4") (pintype "passive"))
      (node (ref "R15") (pin "1") (pinfunction "1_1") (pintype "passive"))
    )
    (net (code "31") (name "Net-(CN1-USBN)") (class "Default")
      (node (ref "CN1") (pin "2") (pinfunction "USBN_2") (pintype "passive"))
      (node (ref "SB11") (pin "1") (pinfunction "1_1") (pintype "passive"))
    )
    (net (code "32") (name "Net-(CN1-USBP)") (class "Default")
      (node (ref "CN1") (pin "3") (pinfunction "USBP_3") (pintype "passive"))
      (node (ref "R12") (pin "1") (pinfunction "1_1") (pintype "passive"))
      (node (ref "SB12") (pin "1") (pinfunction "1_1") (pintype "passive"))
    )
    (net (code "33") (name "Net-(CN1-Vin)") (class "Default")
      (node (ref "CN1") (pin "1") (pinfunction "Vin_1") (pintype "passive"))
      (node (ref "D2") (pin "2") (pinfunction "2_2") (pintype "passive"))
    )
    (net (code "34") (name "Net-(CN2-Pad1)") (class "Default")
      (node (ref "CN2") (pin "1") (pinfunction "1_1") (pintype "passive"))
      (node (ref "D3") (pin "2") (pinfunction "2_2") (pintype "passive"))
      (node (ref "R14") (pin "1") (pinfunction "1_1") (pintype "passive"))
    )
    (net (code "35") (name "Net-(CN2-Pad2)") (class "Default")
      (node (ref "CN2") (pin "2") (pinfunction "2_2") (pintype "passive"))
      (node (ref "R16") (pin "1") (pinfunction "1_1") (pintype "passive"))
    )
    (net (code "36") (name "Net-(CN2-Pad4)") (class "Default")
      (node (ref "CN2") (pin "4") (pinfunction "4_4") (pintype "passive"))
      (node (ref "R17") (pin "1") (pinfunction "1_1") (pintype "passive"))
    )
    (net (code "37") (name "Net-(CN2-Pad5)") (class "Default")
      (node (ref "CN2") (pin "5") (pinfunction "5_5") (pintype "passive"))
      (node (ref "R18") (pin "1") (pinfunction "1_1") (pintype "passive"))
    )
    (net (code "38") (name "Net-(CN2-Pad6)") (class "Default")
      (node (ref "CN2") (pin "6") (pinfunction "6_6") (pintype "passive"))
      (node (ref "R19") (pin "1") (pinfunction "1_1") (pintype "passive"))
    )
    (net (code "39") (name "Net-(LD1-Pad2)") (class "Default")
      (node (ref "LD1") (pin "2") (pinfunction "2_2") (pintype "passive"))
      (node (ref "R10") (pin "2") (pinfunction "2_2") (pintype "passive"))
    )
    (net (code "40") (name "Net-(LD1-Pad3)") (class "Default")
      (node (ref "LD1") (pin "3") (pinfunction "3_3") (pintype "passive"))
      (node (ref "R11") (pin "2") (pinfunction "2_2") (pintype "passive"))
    )
    (net (code "41") (name "Net-(LD1-Pad4)") (class "Default")
      (node (ref "LD1") (pin "4") (pinfunction "4_4") (pintype "passive"))
      (node (ref "SB10") (pin "1") (pinfunction "1_1") (pintype "passive"))
    )
    (net (code "42") (name "Net-(LD2-Pad1)") (class "Default")
      (node (ref "LD2") (pin "1") (pinfunction "1_1") (pintype "passive"))
      (node (ref "R13") (pin "1") (pinfunction "1_1") (pintype "passive"))
    )
    (net (code "43") (name "Net-(U3-BOOT0)") (class "Default")
      (node (ref "R8") (pin "1") (pinfunction "1_1") (pintype "passive"))
      (node (ref "U3") (pin "44") (pinfunction "BOOT0_44") (pintype "passive"))
    )
    (net (code "44") (name "Net-(U3-PA8-MCO)") (class "Default")
      (node (ref "R9") (pin "1") (pinfunction "1_1") (pintype "passive"))
      (node (ref "U3") (pin "29") (pinfunction "PA8-MCO_29") (pintype "passive"))
    )
    (net (code "45") (name "Net-(U3-PC13)") (class "Default")
      (node (ref "R3") (pin "2") (pinfunction "2_2") (pintype "passive"))
      (node (ref "U3") (pin "2") (pinfunction "PC13_2") (pintype "passive"))
    )
    (net (code "46") (name "Net-(U3-PD0-OSC_IN)") (class "Default")
      (node (ref "C31") (pin "1") (pinfunction "1_1") (pintype "passive"))
      (node (ref "U3") (pin "5") (pinfunction "PD0-OSC_IN_5") (pintype "passive"))
      (node (ref "X2") (pin "2") (pinfunction "2_2") (pintype "passive"))
    )
    (net (code "47") (name "Net-(U3-PD1-OSC_OUT)") (class "Default")
      (node (ref "C30") (pin "1") (pinfunction "1_1") (pintype "passive"))
      (node (ref "U3") (pin "6") (pinfunction "PD1-OSC_OUT_6") (pintype "passive"))
      (node (ref "X2") (pin "1") (pinfunction "1_1") (pintype "passive"))
    )
    (net (code "48") (name "Net-(U4-BYPS)") (class "Default")
      (node (ref "C32") (pin "1") (pinfunction "1_1") (pintype "passive"))
      (node (ref "U4") (pin "4") (pinfunction "BYPS_4") (pintype "passive"))
    )
    (net (code "49") (name "Net-(U4-VIN)") (class "Default")
      (node (ref "C33") (pin "2") (pinfunction "2_2") (pintype "passive"))
      (node (ref "C36") (pin "2") (pinfunction "2_2") (pintype "passive"))
      (node (ref "U4") (pin "1") (pinfunction "VIN_1") (pintype "passive"))
      (node (ref "U4") (pin "3") (pinfunction "VINH_3") (pintype "passive"))
    )
    (net (code "50") (name "Net-(U4-VOUT)") (class "Default")
      (node (ref "C34") (pin "2") (pinfunction "2_2") (pintype "passive"))
      (node (ref "C35") (pin "2") (pinfunction "2_2") (pintype "passive"))
      (node (ref "D1") (pin "2") (pinfunction "2_2") (pintype "passive"))
      (node (ref "U4") (pin "5") (pinfunction "VOUT_5") (pintype "passive"))
    )
    (net (code "51") (name "VDD") (class "Default")
      (node (ref "D2") (pin "1") (pinfunction "1_1") (pintype "passive"))
      (node (ref "JP3") (pin "2") (pinfunction "2_2") (pintype "passive"))
    )
    (net (code "52") (name "unconnected-(U3-PA1-Pad11)") (class "Default")
      (node (ref "U3") (pin "11") (pinfunction "PA1_11") (pintype "passive+no_connect"))
    )
    (net (code "53") (name "unconnected-(U3-PA4-Pad14)") (class "Default")
      (node (ref "U3") (pin "14") (pinfunction "PA4_14") (pintype "passive+no_connect"))
    )
    (net (code "54") (name "unconnected-(U3-PA15-Pad38)") (class "Default")
      (node (ref "U3") (pin "38") (pinfunction "PA15_38") (pintype "passive+no_connect"))
    )
    (net (code "55") (name "unconnected-(U3-PB1-Pad19)") (class "Default")
      (node (ref "U3") (pin "19") (pinfunction "PB1_19") (pintype "passive+no_connect"))
    )
    (net (code "56") (name "unconnected-(U3-PB3-Pad39)") (class "Default")
      (node (ref "U3") (pin "39") (pinfunction "PB3_39") (pintype "passive+no_connect"))
    )
    (net (code "57") (name "unconnected-(U3-PB4-Pad40)") (class "Default")
      (node (ref "U3") (pin "40") (pinfunction "PB4_40") (pintype "passive+no_connect"))
    )
    (net (code "58") (name "unconnected-(U3-PB15-Pad28)") (class "Default")
      (node (ref "U3") (pin "28") (pinfunction "PB15_28") (pintype "passive+no_connect"))
    )
    (net (code "59") (name "unconnected-(U3-PC15-Pad4)") (class "Default")
      (node (ref "U3") (pin "4") (pinfunction "PC15_4") (pintype "passive+no_connect"))
    )
  )
)
